# prototype.net
KiCad netlist of a schematic drawn in EAGLE
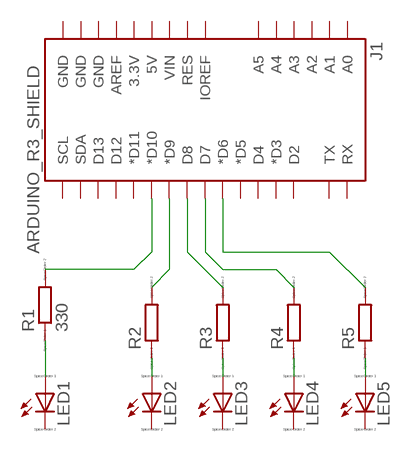
[diagram p0: schematic, sheet 1]

(export (version "E")
  (design (tool "Eeschema 10.0.6"))
  (components
    (comp (ref "J1")
      (value "ARDUINO_R3_SHIELD")
      (footprint "eagle-import:UNO_R3_SHIELD")
      (libsource (lib "eagle-import") (part "ARDUINO_R3_SHIELD"))
    )
    (comp (ref "LED1")
      (value "LED_ELD260")
      (footprint "eagle-import:LED_LD260")
      (libsource (lib "eagle-import") (part "LED_ELD260"))
    )
    (comp (ref "LED2")
      (value "LED_ELD260")
      (footprint "eagle-import:LED_LD260")
      (libsource (lib "eagle-import") (part "LED_ELD260"))
    )
    (comp (ref "LED3")
      (value "LED_ELD260")
      (footprint "eagle-import:LED_LD260")
      (libsource (lib "eagle-import") (part "LED_ELD260"))
    )
    (comp (ref "LED4")
      (value "LED_ELD260")
      (footprint "eagle-import:LED_LD260")
      (libsource (lib "eagle-import") (part "LED_ELD260"))
    )
    (comp (ref "LED5")
      (value "LED_ELD260")
      (footprint "eagle-import:LED_LD260")
      (libsource (lib "eagle-import") (part "LED_ELD260"))
    )
    (comp (ref "R1")
      (value "330")
      (footprint "eagle-import:0207_10")
      (libsource (lib "eagle-import") (part "R0207/10"))
    )
    (comp (ref "R2")
      (value "R0207/10")
      (footprint "eagle-import:0207_10")
      (libsource (lib "eagle-import") (part "R0207/10"))
    )
    (comp (ref "R3")
      (value "R0207/10")
      (footprint "eagle-import:0207_10")
      (libsource (lib "eagle-import") (part "R0207/10"))
    )
    (comp (ref "R4")
      (value "R0207/10")
      (footprint "eagle-import:0207_10")
      (libsource (lib "eagle-import") (part "R0207/10"))
    )
    (comp (ref "R5")
      (value "R0207/10")
      (footprint "eagle-import:0207_10")
      (libsource (lib "eagle-import") (part "R0207/10"))
    )
  )
  (nets
    (net (code "1") (name "Net-(J1-*D6)") (class "Default")
      (node (ref "J1") (pin "D6") (pinfunction "*D6_D6") (pintype "bidirectional"))
      (node (ref "R5") (pin "2") (pinfunction "2_2") (pintype "passive"))
    )
    (net (code "2") (name "Net-(J1-*D9)") (class "Default")
      (node (ref "J1") (pin "D9") (pinfunction "*D9_D9") (pintype "bidirectional"))
      (node (ref "R2") (pin "2") (pinfunction "2_2") (pintype "passive"))
    )
    (net (code "3") (name "Net-(J1-*D10)") (class "Default")
      (node (ref "J1") (pin "D10") (pinfunction "*D10_D10") (pintype "bidirectional"))
      (node (ref "R1") (pin "2") (pinfunction "2_2") (pintype "passive"))
    )
    (net (code "4") (name "Net-(J1-PadD7)") (class "Default")
      (node (ref "J1") (pin "D7") (pinfunction "D7_D7") (pintype "bidirectional"))
      (node (ref "R4") (pin "2") (pinfunction "2_2") (pintype "passive"))
    )
    (net (code "5") (name "Net-(J1-PadD8)") (class "Default")
      (node (ref "J1") (pin "D8") (pinfunction "D8_D8") (pintype "bidirectional"))
      (node (ref "R3") (pin "2") (pinfunction "2_2") (pintype "passive"))
    )
    (net (code "6") (name "Net-(LED1-PadA)") (class "Default")
      (node (ref "LED1") (pin "A") (pinfunction "A_A") (pintype "passive"))
      (node (ref "R1") (pin "1") (pinfunction "1_1") (pintype "passive"))
    )
    (net (code "7") (name "Net-(LED2-PadA)") (class "Default")
      (node (ref "LED2") (pin "A") (pinfunction "A_A") (pintype "passive"))
      (node (ref "R2") (pin "1") (pinfunction "1_1") (pintype "passive"))
    )
    (net (code "8") (name "Net-(LED3-PadA)") (class "Default")
      (node (ref "LED3") (pin "A") (pinfunction "A_A") (pintype "passive"))
      (node (ref "R3") (pin "1") (pinfunction "1_1") (pintype "passive"))
    )
    (net (code "9") (name "Net-(LED4-PadA)") (class "Default")
      (node (ref "LED4") (pin "A") (pinfunction "A_A") (pintype "passive"))
      (node (ref "R4") (pin "1") (pinfunction "1_1") (pintype "passive"))
    )
    (net (code "10") (name "Net-(LED5-PadA)") (class "Default")
      (node (ref "LED5") (pin "A") (pinfunction "A_A") (pintype "passive"))
      (node (ref "R5") (pin "1") (pinfunction "1_1") (pintype "passive"))
    )
    (net (code "11") (name "unconnected-(J1-*D3-PadD3)") (class "Default")
      (node (ref "J1") (pin "D3") (pinfunction "*D3_D3") (pintype "bidirectional"))
    )
    (net (code "12") (name "unconnected-(J1-*D5-PadD5)") (class "Default")
      (node (ref "J1") (pin "D5") (pinfunction "*D5_D5") (pintype "bidirectional"))
    )
    (net (code "13") (name "unconnected-(J1-*D11-PadD11)") (class "Default")
      (node (ref "J1") (pin "D11") (pinfunction "*D11_D11") (pintype "bidirectional"))
    )
    (net (code "14") (name "unconnected-(J1-GND-PadGND@0)") (class "Default")
      (node (ref "J1") (pin "GND@0") (pinfunction "GND_GND@0") (pintype "bidirectional"))
    )
    (net (code "15") (name "unconnected-(J1-GND-PadGND@1)") (class "Default")
      (node (ref "J1") (pin "GND@1") (pinfunction "GND_GND@1") (pintype "bidirectional"))
    )
    (net (code "16") (name "unconnected-(J1-GND-PadGND@2)") (class "Default")
      (node (ref "J1") (pin "GND@2") (pinfunction "GND_GND@2") (pintype "bidirectional"))
    )
    (net (code "17") (name "unconnected-(J1-Pad3.3V)") (class "Default")
      (node (ref "J1") (pin "3.3V") (pinfunction "3.3V_3.3V") (pintype "bidirectional"))
    )
    (net (code "18") (name "unconnected-(J1-Pad5V)") (class "Default")
      (node (ref "J1") (pin "5V") (pinfunction "5V_5V") (pintype "bidirectional"))
    )
    (net (code "19") (name "unconnected-(J1-PadA0)") (class "Default")
      (node (ref "J1") (pin "A0") (pinfunction "A0_A0") (pintype "bidirectional"))
    )
    (net (code "20") (name "unconnected-(J1-PadA1)") (class "Default")
      (node (ref "J1") (pin "A1") (pinfunction "A1_A1") (pintype "bidirectional"))
    )
    (net (code "21") (name "unconnected-(J1-PadA2)") (class "Default")
      (node (ref "J1") (pin "A2") (pinfunction "A2_A2") (pintype "bidirectional"))
    )
    (net (code "22") (name "unconnected-(J1-PadA3)") (class "Default")
      (node (ref "J1") (pin "A3") (pinfunction "A3_A3") (pintype "bidirectional"))
    )
    (net (code "23") (name "unconnected-(J1-PadA4)") (class "Default")
      (node (ref "J1") (pin "A4") (pinfunction "A4_A4") (pintype "bidirectional"))
    )
    (net (code "24") (name "unconnected-(J1-PadA5)") (class "Default")
      (node (ref "J1") (pin "A5") (pinfunction "A5_A5") (pintype "bidirectional"))
    )
    (net (code "25") (name "unconnected-(J1-PadAREF)") (class "Default")
      (node (ref "J1") (pin "AREF") (pinfunction "AREF_AREF") (pintype "bidirectional"))
    )
    (net (code "26") (name "unconnected-(J1-PadD2)") (class "Default")
      (node (ref "J1") (pin "D2") (pinfunction "D2_D2") (pintype "bidirectional"))
    )
    (net (code "27") (name "unconnected-(J1-PadD4)") (class "Default")
      (node (ref "J1") (pin "D4") (pinfunction "D4_D4") (pintype "bidirectional"))
    )
    (net (code "28") (name "unconnected-(J1-PadD12)") (class "Default")
      (node (ref "J1") (pin "D12") (pinfunction "D12_D12") (pintype "bidirectional"))
    )
    (net (code "29") (name "unconnected-(J1-PadD13)") (class "Default")
      (node (ref "J1") (pin "D13") (pinfunction "D13_D13") (pintype "bidirectional"))
    )
    (net (code "30") (name "unconnected-(J1-PadIOREF)") (class "Default")
      (node (ref "J1") (pin "IOREF") (pinfunction "IOREF_IOREF") (pintype "bidirectional"))
    )
    (net (code "31") (name "unconnected-(J1-PadRES)") (class "Default")
      (node (ref "J1") (pin "RES") (pinfunction "RES_RES") (pintype "bidirectional"))
    )
    (net (code "32") (name "unconnected-(J1-PadRX)") (class "Default")
      (node (ref "J1") (pin "RX") (pinfunction "RX_RX") (pintype "bidirectional"))
    )
    (net (code "33") (name "unconnected-(J1-PadSCL)") (class "Default")
      (node (ref "J1") (pin "SCL") (pinfunction "SCL_SCL") (pintype "bidirectional"))
    )
    (net (code "34") (name "unconnected-(J1-PadSDA)") (class "Default")
      (node (ref "J1") (pin "SDA") (pinfunction "SDA_SDA") (pintype "bidirectional"))
    )
    (net (code "35") (name "unconnected-(J1-PadTX)") (class "Default")
      (node (ref "J1") (pin "TX") (pinfunction "TX_TX") (pintype "bidirectional"))
    )
    (net (code "36") (name "unconnected-(J1-PadVIN)") (class "Default")
      (node (ref "J1") (pin "VIN") (pinfunction "VIN_VIN") (pintype "bidirectional"))
    )
    (net (code "37") (name "unconnected-(LED1-C-PadK)") (class "Default")
      (node (ref "LED1") (pin "K") (pinfunction "C_K") (pintype "passive"))
    )
    (net (code "38") (name "unconnected-(LED2-C-PadK)") (class "Default")
      (node (ref "LED2") (pin "K") (pinfunction "C_K") (pintype "passive"))
    )
    (net (code "39") (name "unconnected-(LED3-C-PadK)") (class "Default")
      (node (ref "LED3") (pin "K") (pinfunction "C_K") (pintype "passive"))
    )
    (net (code "40") (name "unconnected-(LED4-C-PadK)") (class "Default")
      (node (ref "LED4") (pin "K") (pinfunction "C_K") (pintype "passive"))
    )
    (net (code "41") (name "unconnected-(LED5-C-PadK)") (class "Default")
      (node (ref "LED5") (pin "K") (pinfunction "C_K") (pintype "passive"))
    )
  )
)
